# L6470Breakout.net
KiCad netlist of a schematic drawn in EAGLE
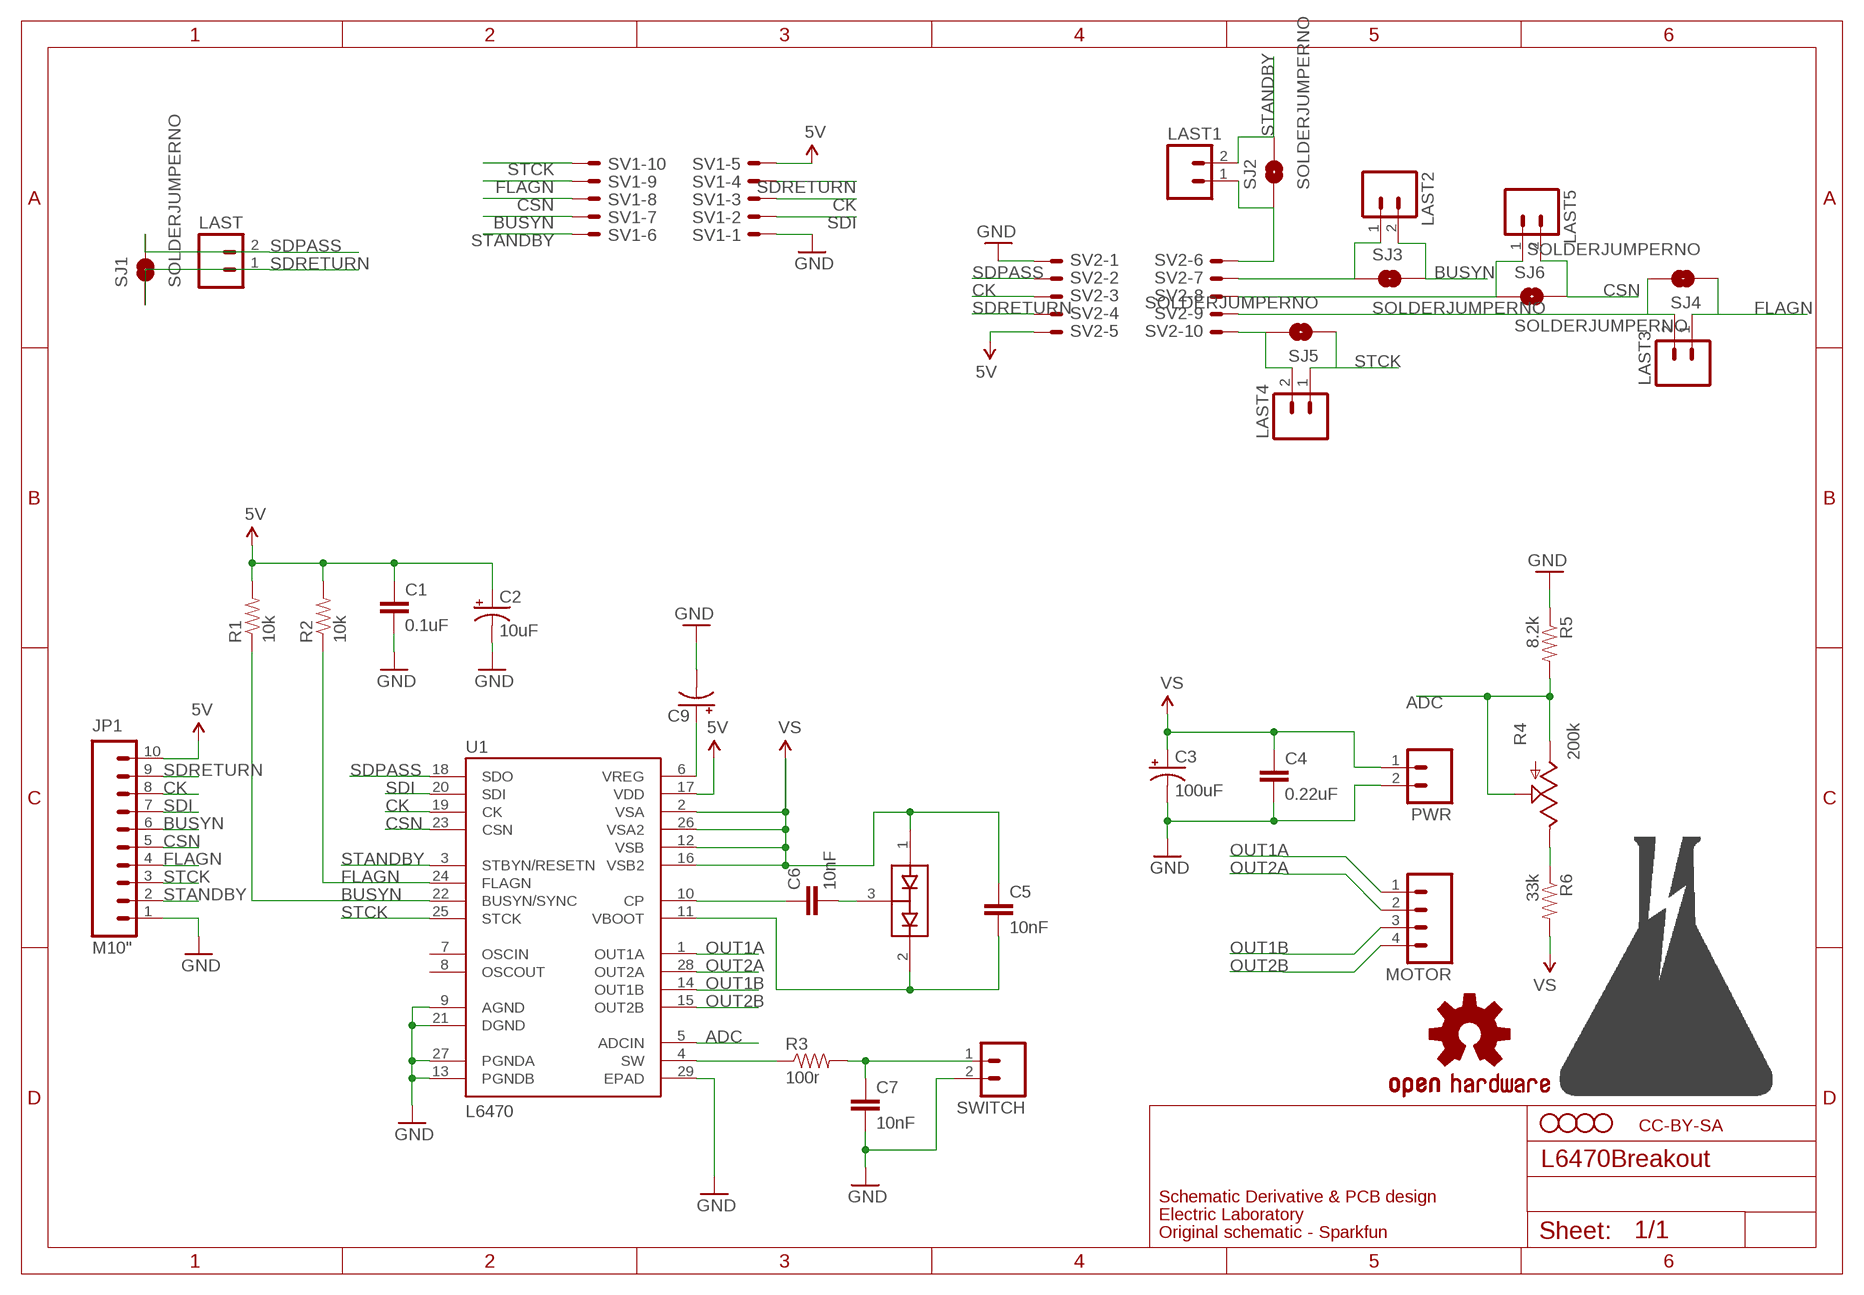
[diagram p0: schematic, sheet 1]

(export (version "E")
  (design (tool "Eeschema 10.0.6"))
  (components
    (comp (ref "C1")
      (value "0.1uF")
      (footprint "eagle-import:0603-CAP")
      (libsource (lib "eagle-import") (part "SparkFun-Passives_CAP0603-CAP"))
    )
    (comp (ref "C2")
      (value "10uF")
      (footprint "eagle-import:EIA3216")
      (libsource (lib "eagle-import") (part "CAP_POL1206"))
    )
    (comp (ref "C3")
      (value "100uF")
      (footprint "eagle-import:PANASONIC_H13")
      (libsource (lib "eagle-import") (part "miscellany_CAP_POLH13"))
    )
    (comp (ref "C4")
      (value "0.22uF")
      (footprint "eagle-import:0603-CAP")
      (libsource (lib "eagle-import") (part "CAP0603-CAP"))
    )
    (comp (ref "C5")
      (value "10nF")
      (footprint "eagle-import:0603-CAP")
      (libsource (lib "eagle-import") (part "SparkFun-Passives_CAP0603-CAP"))
    )
    (comp (ref "C6")
      (value "10nF")
      (footprint "eagle-import:0603-CAP")
      (libsource (lib "eagle-import") (part "SparkFun-Passives_CAP0603-CAP"))
    )
    (comp (ref "C7")
      (value "10nF")
      (footprint "eagle-import:0603-CAP")
      (libsource (lib "eagle-import") (part "SparkFun-Passives_CAP0603-CAP"))
    )
    (comp (ref "C9")
      (value "CAP_POL1206")
      (footprint "eagle-import:EIA3216")
      (libsource (lib "eagle-import") (part "SparkFun-Passives_CAP_POL1206"))
    )
    (comp (ref "D1")
      (value "BAV99")
      (footprint "eagle-import:SOT23")
      (libsource (lib "eagle-import") (part "BAV99"))
    )
    (comp (ref "JP1")
      (value "M10\"")
      (footprint "eagle-import:1X10")
      (libsource (lib "eagle-import") (part "M10{dblquote}"))
    )
    (comp (ref "JP3")
      (value "STAND-OFF")
      (footprint "eagle-import:STAND-OFF")
      (libsource (lib "eagle-import") (part "STAND-OFF"))
    )
    (comp (ref "JP4")
      (value "STAND-OFF")
      (footprint "eagle-import:STAND-OFF")
      (libsource (lib "eagle-import") (part "STAND-OFF"))
    )
    (comp (ref "JP6")
      (value "STAND-OFF")
      (footprint "eagle-import:STAND-OFF")
      (libsource (lib "eagle-import") (part "STAND-OFF"))
    )
    (comp (ref "JP7")
      (value "STAND-OFF")
      (footprint "eagle-import:STAND-OFF")
      (libsource (lib "eagle-import") (part "STAND-OFF"))
    )
    (comp (ref "LAST")
      (value "M02PTH")
      (footprint "eagle-import:1X02")
      (libsource (lib "eagle-import") (part "SparkFun-Connectors_M02PTH"))
    )
    (comp (ref "LAST1")
      (value "M02PTH")
      (footprint "eagle-import:1X02")
      (libsource (lib "eagle-import") (part "SparkFun-Connectors_M02PTH"))
    )
    (comp (ref "LAST2")
      (value "M02PTH")
      (footprint "eagle-import:1X02")
      (libsource (lib "eagle-import") (part "SparkFun-Connectors_M02PTH"))
    )
    (comp (ref "LAST3")
      (value "M02PTH")
      (footprint "eagle-import:1X02")
      (libsource (lib "eagle-import") (part "SparkFun-Connectors_M02PTH"))
    )
    (comp (ref "LAST4")
      (value "M02PTH")
      (footprint "eagle-import:1X02")
      (libsource (lib "eagle-import") (part "SparkFun-Connectors_M02PTH"))
    )
    (comp (ref "LAST5")
      (value "M02PTH")
      (footprint "eagle-import:1X02")
      (libsource (lib "eagle-import") (part "SparkFun-Connectors_M02PTH"))
    )
    (comp (ref "MOTOR")
      (value "M04SCREW")
      (footprint "eagle-import:SCREWTERMINAL-3.5MM-4")
      (libsource (lib "eagle-import") (part "M04SCREW"))
    )
    (comp (ref "PWR")
      (value "M023.5MM")
      (footprint "eagle-import:SCREWTERMINAL-3.5MM-2")
      (libsource (lib "eagle-import") (part "M023.5MM"))
    )
    (comp (ref "R1")
      (value "10k")
      (footprint "eagle-import:0603-RES")
      (libsource (lib "eagle-import") (part "RESISTOR0603-RES"))
    )
    (comp (ref "R2")
      (value "10k")
      (footprint "eagle-import:0603-RES")
      (libsource (lib "eagle-import") (part "RESISTOR0603-RES"))
    )
    (comp (ref "R3")
      (value "100r")
      (footprint "eagle-import:0603-RES")
      (libsource (lib "eagle-import") (part "RESISTOR0603-RES"))
    )
    (comp (ref "R4")
      (value "200k")
      (footprint "eagle-import:3362U")
      (libsource (lib "eagle-import") (part "POT100K_3362U"))
    )
    (comp (ref "R5")
      (value "8.2k")
      (footprint "eagle-import:0603-RES")
      (libsource (lib "eagle-import") (part "RESISTOR0603-RES"))
    )
    (comp (ref "R6")
      (value "33k")
      (footprint "eagle-import:0603-RES")
      (libsource (lib "eagle-import") (part "RESISTOR0603-RES"))
    )
    (comp (ref "SJ1")
      (value "SOLDERJUMPERNO")
      (footprint "eagle-import:SJ_2S-NO")
      (libsource (lib "eagle-import") (part "SOLDERJUMPERNO"))
    )
    (comp (ref "SJ2")
      (value "SOLDERJUMPERNO")
      (footprint "eagle-import:SJ_2S-NO")
      (libsource (lib "eagle-import") (part "SOLDERJUMPERNO"))
    )
    (comp (ref "SJ3")
      (value "SOLDERJUMPERNO")
      (footprint "eagle-import:SJ_2S-NO")
      (libsource (lib "eagle-import") (part "SOLDERJUMPERNO"))
    )
    (comp (ref "SJ4")
      (value "SOLDERJUMPERNO")
      (footprint "eagle-import:SJ_2S-NO")
      (libsource (lib "eagle-import") (part "SOLDERJUMPERNO"))
    )
    (comp (ref "SJ5")
      (value "SOLDERJUMPERNO")
      (footprint "eagle-import:SJ_2S-NO")
      (libsource (lib "eagle-import") (part "SOLDERJUMPERNO"))
    )
    (comp (ref "SJ6")
      (value "SOLDERJUMPERNO")
      (footprint "eagle-import:SJ_2S-NO")
      (libsource (lib "eagle-import") (part "SOLDERJUMPERNO"))
    )
    (comp (ref "SV1")
      (value "ML10E")
      (footprint "eagle-import:ML10")
      (libsource (lib "eagle-import") (part "ML10?E"))
    )
    (comp (ref "SV2")
      (value "ML10E")
      (footprint "eagle-import:ML10")
      (libsource (lib "eagle-import") (part "ML10?E"))
    )
    (comp (ref "SWITCH")
      (value "M023.5MM")
      (footprint "eagle-import:SCREWTERMINAL-3.5MM-2")
      (libsource (lib "eagle-import") (part "M023.5MM"))
    )
    (comp (ref "U$4")
      (value "OSHW-LOGOS")
      (footprint "eagle-import:OSHW-LOGO-S")
      (libsource (lib "eagle-import") (part "OSHW-LOGOS"))
    )
    (comp (ref "U$5")
      (value "EL-LOGO")
      (footprint "eagle-import:EL-LOGO")
      (libsource (lib "eagle-import") (part "EL-LOGO"))
    )
    (comp (ref "U1")
      (value "L6470")
      (footprint "eagle-import:HTSSOP28")
      (libsource (lib "eagle-import") (part "L6470"))
    )
  )
  (nets
    (net (code "1") (name "/ADC") (class "Default")
      (node (ref "R4") (pin "P$2") (pinfunction "S_P$2") (pintype "passive"))
      (node (ref "R4") (pin "P$3") (pinfunction "A_P$3") (pintype "passive"))
      (node (ref "R5") (pin "2") (pinfunction "2_2") (pintype "passive"))
      (node (ref "U1") (pin "5") (pinfunction "ADCIN_5") (pintype "bidirectional"))
    )
    (net (code "2") (name "/BUSYN") (class "Default")
      (node (ref "JP1") (pin "6") (pinfunction "6_6") (pintype "passive"))
      (node (ref "LAST2") (pin "2") (pinfunction "2_2") (pintype "passive"))
      (node (ref "R1") (pin "1") (pinfunction "1_1") (pintype "passive"))
      (node (ref "SJ3") (pin "2") (pinfunction "2_2") (pintype "passive"))
      (node (ref "SV1") (pin "7") (pinfunction "S_7") (pintype "passive"))
      (node (ref "U1") (pin "22") (pinfunction "BUSYN/SYNC_22") (pintype "bidirectional"))
    )
    (net (code "3") (name "/CK") (class "Default")
      (node (ref "JP1") (pin "8") (pinfunction "8_8") (pintype "passive"))
      (node (ref "SV1") (pin "3") (pinfunction "S_3") (pintype "passive"))
      (node (ref "SV2") (pin "3") (pinfunction "S_3") (pintype "passive"))
      (node (ref "U1") (pin "19") (pinfunction "CK_19") (pintype "bidirectional"))
    )
    (net (code "4") (name "/CSN") (class "Default")
      (node (ref "JP1") (pin "5") (pinfunction "5_5") (pintype "passive"))
      (node (ref "LAST5") (pin "2") (pinfunction "2_2") (pintype "passive"))
      (node (ref "SJ6") (pin "2") (pinfunction "2_2") (pintype "passive"))
      (node (ref "SV1") (pin "8") (pinfunction "S_8") (pintype "passive"))
      (node (ref "U1") (pin "23") (pinfunction "CSN_23") (pintype "bidirectional"))
    )
    (net (code "5") (name "/FLAGN") (class "Default")
      (node (ref "JP1") (pin "4") (pinfunction "4_4") (pintype "passive"))
      (node (ref "LAST3") (pin "1") (pinfunction "1_1") (pintype "passive"))
      (node (ref "R2") (pin "1") (pinfunction "1_1") (pintype "passive"))
      (node (ref "SJ4") (pin "1") (pinfunction "1_1") (pintype "passive"))
      (node (ref "SV1") (pin "9") (pinfunction "S_9") (pintype "passive"))
      (node (ref "U1") (pin "24") (pinfunction "FLAGN_24") (pintype "bidirectional"))
    )
    (net (code "6") (name "/OUT1A") (class "Default")
      (node (ref "MOTOR") (pin "1") (pinfunction "1_1") (pintype "passive"))
      (node (ref "U1") (pin "1") (pinfunction "OUT1A_1") (pintype "bidirectional"))
    )
    (net (code "7") (name "/OUT1B") (class "Default")
      (node (ref "MOTOR") (pin "3") (pinfunction "3_3") (pintype "passive"))
      (node (ref "U1") (pin "14") (pinfunction "OUT1B_14") (pintype "bidirectional"))
    )
    (net (code "8") (name "/OUT2A") (class "Default")
      (node (ref "MOTOR") (pin "2") (pinfunction "2_2") (pintype "passive"))
      (node (ref "U1") (pin "28") (pinfunction "OUT2A_28") (pintype "bidirectional"))
    )
    (net (code "9") (name "/OUT2B") (class "Default")
      (node (ref "MOTOR") (pin "4") (pinfunction "4_4") (pintype "passive"))
      (node (ref "U1") (pin "15") (pinfunction "OUT2B_15") (pintype "bidirectional"))
    )
    (net (code "10") (name "/SDI") (class "Default")
      (node (ref "JP1") (pin "7") (pinfunction "7_7") (pintype "passive"))
      (node (ref "SV1") (pin "2") (pinfunction "S_2") (pintype "passive"))
      (node (ref "U1") (pin "20") (pinfunction "SDI_20") (pintype "bidirectional"))
    )
    (net (code "11") (name "/SDPASS") (class "Default")
      (node (ref "LAST") (pin "2") (pinfunction "2_2") (pintype "passive"))
      (node (ref "SJ1") (pin "2") (pinfunction "2_2") (pintype "passive"))
      (node (ref "SV2") (pin "2") (pinfunction "S_2") (pintype "passive"))
      (node (ref "U1") (pin "18") (pinfunction "SDO_18") (pintype "bidirectional"))
    )
    (net (code "12") (name "/SDRETURN") (class "Default")
      (node (ref "JP1") (pin "9") (pinfunction "9_9") (pintype "passive"))
      (node (ref "LAST") (pin "1") (pinfunction "1_1") (pintype "passive"))
      (node (ref "SJ1") (pin "1") (pinfunction "1_1") (pintype "passive"))
      (node (ref "SV1") (pin "4") (pinfunction "S_4") (pintype "passive"))
      (node (ref "SV2") (pin "4") (pinfunction "S_4") (pintype "passive"))
    )
    (net (code "13") (name "/STANDBY") (class "Default")
      (node (ref "JP1") (pin "2") (pinfunction "2_2") (pintype "passive"))
      (node (ref "LAST1") (pin "2") (pinfunction "2_2") (pintype "passive"))
      (node (ref "SJ2") (pin "2") (pinfunction "2_2") (pintype "passive"))
      (node (ref "SV1") (pin "6") (pinfunction "S_6") (pintype "passive"))
      (node (ref "U1") (pin "3") (pinfunction "STBYN/RESETN_3") (pintype "bidirectional"))
    )
    (net (code "14") (name "/STCK") (class "Default")
      (node (ref "JP1") (pin "3") (pinfunction "3_3") (pintype "passive"))
      (node (ref "LAST4") (pin "1") (pinfunction "1_1") (pintype "passive"))
      (node (ref "SJ5") (pin "1") (pinfunction "1_1") (pintype "passive"))
      (node (ref "SV1") (pin "10") (pinfunction "S_10") (pintype "passive"))
      (node (ref "U1") (pin "25") (pinfunction "STCK_25") (pintype "bidirectional"))
    )
    (net (code "15") (name "5V") (class "Default")
      (node (ref "C1") (pin "1") (pinfunction "1_1") (pintype "passive"))
      (node (ref "C2") (pin "A") (pinfunction "+_A") (pintype "passive"))
      (node (ref "JP1") (pin "10") (pinfunction "10_10") (pintype "passive"))
      (node (ref "R1") (pin "2") (pinfunction "2_2") (pintype "passive"))
      (node (ref "R2") (pin "2") (pinfunction "2_2") (pintype "passive"))
      (node (ref "SV1") (pin "5") (pinfunction "S_5") (pintype "passive"))
      (node (ref "SV2") (pin "5") (pinfunction "S_5") (pintype "passive"))
      (node (ref "U1") (pin "17") (pinfunction "VDD_17") (pintype "bidirectional"))
    )
    (net (code "16") (name "GND") (class "Default")
      (node (ref "C1") (pin "2") (pinfunction "2_2") (pintype "passive"))
      (node (ref "C2") (pin "C") (pinfunction "-_C") (pintype "passive"))
      (node (ref "C3") (pin "-") (pinfunction "-_-") (pintype "passive"))
      (node (ref "C4") (pin "2") (pinfunction "2_2") (pintype "passive"))
      (node (ref "C7") (pin "2") (pinfunction "2_2") (pintype "passive"))
      (node (ref "C9") (pin "C") (pinfunction "-_C") (pintype "passive"))
      (node (ref "JP1") (pin "1") (pinfunction "1_1") (pintype "passive"))
      (node (ref "PWR") (pin "2") (pinfunction "2_2") (pintype "passive"))
      (node (ref "R5") (pin "1") (pinfunction "1_1") (pintype "passive"))
      (node (ref "SV1") (pin "1") (pinfunction "S_1") (pintype "passive"))
      (node (ref "SV2") (pin "1") (pinfunction "S_1") (pintype "passive"))
      (node (ref "SWITCH") (pin "2") (pinfunction "2_2") (pintype "passive"))
      (node (ref "U1") (pin "13") (pinfunction "PGNDB_13") (pintype "bidirectional"))
      (node (ref "U1") (pin "21") (pinfunction "DGND_21") (pintype "bidirectional"))
      (node (ref "U1") (pin "27") (pinfunction "PGNDA_27") (pintype "bidirectional"))
      (node (ref "U1") (pin "29") (pinfunction "EPAD_29") (pintype "bidirectional"))
      (node (ref "U1") (pin "9") (pinfunction "AGND_9") (pintype "bidirectional"))
    )
    (net (code "17") (name "Net-(C7-Pad1)") (class "Default")
      (node (ref "C7") (pin "1") (pinfunction "1_1") (pintype "passive"))
      (node (ref "R3") (pin "2") (pinfunction "2_2") (pintype "passive"))
      (node (ref "SWITCH") (pin "1") (pinfunction "1_1") (pintype "passive"))
    )
    (net (code "18") (name "Net-(C9-+)") (class "Default")
      (node (ref "C9") (pin "A") (pinfunction "+_A") (pintype "passive"))
      (node (ref "U1") (pin "6") (pinfunction "VREG_6") (pintype "bidirectional"))
    )
    (net (code "19") (name "Net-(D1-C2)") (class "Default")
      (node (ref "C5") (pin "2") (pinfunction "2_2") (pintype "passive"))
      (node (ref "D1") (pin "2") (pinfunction "C2_2") (pintype "bidirectional"))
      (node (ref "U1") (pin "11") (pinfunction "VBOOT_11") (pintype "bidirectional"))
    )
    (net (code "20") (name "Net-(D1-COM)") (class "Default")
      (node (ref "C6") (pin "2") (pinfunction "2_2") (pintype "passive"))
      (node (ref "D1") (pin "3") (pinfunction "COM_3") (pintype "bidirectional"))
    )
    (net (code "21") (name "Net-(R4-E)") (class "Default")
      (node (ref "R4") (pin "P$1") (pinfunction "E_P$1") (pintype "passive"))
      (node (ref "R6") (pin "1") (pinfunction "1_1") (pintype "passive"))
    )
    (net (code "22") (name "Net-(SV2B-S)") (class "Default")
      (node (ref "LAST4") (pin "2") (pinfunction "2_2") (pintype "passive"))
      (node (ref "SJ5") (pin "2") (pinfunction "2_2") (pintype "passive"))
      (node (ref "SV2") (pin "10") (pinfunction "S_10") (pintype "passive"))
    )
    (net (code "23") (name "Net-(SV2G-S)") (class "Default")
      (node (ref "LAST1") (pin "1") (pinfunction "1_1") (pintype "passive"))
      (node (ref "SJ2") (pin "1") (pinfunction "1_1") (pintype "passive"))
      (node (ref "SV2") (pin "6") (pinfunction "S_6") (pintype "passive"))
    )
    (net (code "24") (name "Net-(SV2H-S)") (class "Default")
      (node (ref "LAST2") (pin "1") (pinfunction "1_1") (pintype "passive"))
      (node (ref "SJ3") (pin "1") (pinfunction "1_1") (pintype "passive"))
      (node (ref "SV2") (pin "7") (pinfunction "S_7") (pintype "passive"))
    )
    (net (code "25") (name "Net-(SV2I-S)") (class "Default")
      (node (ref "LAST5") (pin "1") (pinfunction "1_1") (pintype "passive"))
      (node (ref "SJ6") (pin "1") (pinfunction "1_1") (pintype "passive"))
      (node (ref "SV2") (pin "8") (pinfunction "S_8") (pintype "passive"))
    )
    (net (code "26") (name "Net-(SV2J-S)") (class "Default")
      (node (ref "LAST3") (pin "2") (pinfunction "2_2") (pintype "passive"))
      (node (ref "SJ4") (pin "2") (pinfunction "2_2") (pintype "passive"))
      (node (ref "SV2") (pin "9") (pinfunction "S_9") (pintype "passive"))
    )
    (net (code "27") (name "Net-(U1-CP)") (class "Default")
      (node (ref "C6") (pin "1") (pinfunction "1_1") (pintype "passive"))
      (node (ref "U1") (pin "10") (pinfunction "CP_10") (pintype "bidirectional"))
    )
    (net (code "28") (name "Net-(U1-SW)") (class "Default")
      (node (ref "R3") (pin "1") (pinfunction "1_1") (pintype "passive"))
      (node (ref "U1") (pin "4") (pinfunction "SW_4") (pintype "bidirectional"))
    )
    (net (code "29") (name "VS") (class "Default")
      (node (ref "C3") (pin "+") (pinfunction "+_+") (pintype "passive"))
      (node (ref "C4") (pin "1") (pinfunction "1_1") (pintype "passive"))
      (node (ref "C5") (pin "1") (pinfunction "1_1") (pintype "passive"))
      (node (ref "D1") (pin "1") (pinfunction "A1_1") (pintype "bidirectional"))
      (node (ref "PWR") (pin "1") (pinfunction "1_1") (pintype "passive"))
      (node (ref "R6") (pin "2") (pinfunction "2_2") (pintype "passive"))
      (node (ref "U1") (pin "12") (pinfunction "VSB_12") (pintype "bidirectional"))
      (node (ref "U1") (pin "16") (pinfunction "VSB2_16") (pintype "bidirectional"))
      (node (ref "U1") (pin "2") (pinfunction "VSA_2") (pintype "bidirectional"))
      (node (ref "U1") (pin "26") (pinfunction "VSA2_26") (pintype "bidirectional"))
    )
    (net (code "30") (name "unconnected-(U1-OSCIN-Pad7)") (class "Default")
      (node (ref "U1") (pin "7") (pinfunction "OSCIN_7") (pintype "bidirectional"))
    )
    (net (code "31") (name "unconnected-(U1-OSCOUT-Pad8)") (class "Default")
      (node (ref "U1") (pin "8") (pinfunction "OSCOUT_8") (pintype "bidirectional"))
    )
  )
)
